# Antenna_Network.net
KiCad netlist of a schematic drawn in Altium Designer
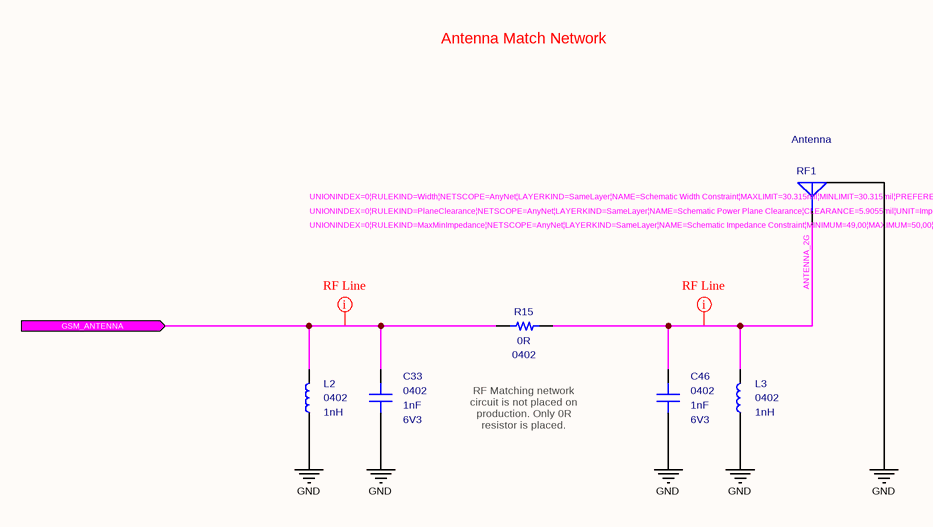
[diagram p0: Antenna Network.SchDoc]

(export (version "E")
  (design (tool "Eeschema 10.0.6"))
  (components
    (comp (ref "C33")
      (value "1nF")
      (footprint "CAPACITOR_0402")
      (description "Capacitor - 1nF [0402] (Ceramic)")
      (fields
        (field (name "MANUFACTURER_PART_NUMBER") "04026C102MAT2A")
        (field (name "MOUSER_PART_NUMBER") "581-04026C102MAT2A")
        (field (name "CASE") "0402")
        (field (name "VOLTAGE") "6V3")
      )
      (libsource (lib "Ovoo_Schematic") (part "Capacitor - 1nF [0402-6V3)"))
    )
    (comp (ref "C46")
      (value "1nF")
      (footprint "CAPACITOR_0402")
      (description "Capacitor - 1nF [0402] (Ceramic)")
      (fields
        (field (name "MANUFACTURER_PART_NUMBER") "04026C102MAT2A")
        (field (name "MOUSER_PART_NUMBER") "581-04026C102MAT2A")
        (field (name "CASE") "0402")
        (field (name "VOLTAGE") "6V3")
      )
      (libsource (lib "Ovoo_Schematic") (part "Capacitor - 1nF [0402-6V3)"))
    )
    (comp (ref "L2")
      (value "1nH")
      (footprint "INDUCTOR_0402")
      (description "Fixed Inductor")
      (fields
        (field (name "MANUFACTURER_PART_NUMBER") "LQG15HN1N0S02D")
        (field (name "MOUSER_PART_NUMBER") "81-LQG15HN1N0S02D")
        (field (name "CASE") "0402")
      )
      (libsource (lib "Ovoo_Schematic") (part "Inductor - 1nH [0402]"))
    )
    (comp (ref "L3")
      (value "1nH")
      (footprint "INDUCTOR_0402")
      (description "Fixed Inductor")
      (fields
        (field (name "MANUFACTURER_PART_NUMBER") "LQG15HN1N0S02D")
        (field (name "MOUSER_PART_NUMBER") "81-LQG15HN1N0S02D")
        (field (name "CASE") "0402")
      )
      (libsource (lib "Ovoo_Schematic") (part "Inductor - 1nH [0402]"))
    )
    (comp (ref "R15")
      (value "0R")
      (footprint "RESISTOR_0402")
      (description "Thick Film Resistors - SMD 1/16 W 0 Ohms")
      (fields
        (field (name "MANUFACTURER_PART_NUMBER") "CRCW04020000Z0ED")
        (field (name "MOUSER_PART_NUMBER") "71-CRCW0402-0-E3")
        (field (name "CASE") "0402")
      )
      (libsource (lib "Ovoo_Schematic") (part "Resistor - 0R"))
    )
    (comp (ref "RF1")
      (value "Antenna")
      (footprint "Connector_IPEX")
      (description "MHF Antenna Socket")
      (libsource (lib "Ovoo_Schematic") (part "Connector - MHF"))
    )
  )
  (nets
    (net (code "1") (name "/ANTENNA_2G") (class "Default")
      (node (ref "C46") (pin "2") (pinfunction "2_2") (pintype "passive"))
      (node (ref "L3") (pin "2") (pinfunction "2_2") (pintype "passive"))
      (node (ref "R15") (pin "1") (pinfunction "1_1") (pintype "passive"))
      (node (ref "RF1") (pin "1") (pinfunction "Signal_1") (pintype "passive"))
    )
    (net (code "2") (name "/GSM_ANTENNA") (class "Default")
      (node (ref "C33") (pin "2") (pinfunction "2_2") (pintype "passive"))
      (node (ref "L2") (pin "2") (pinfunction "2_2") (pintype "passive"))
      (node (ref "R15") (pin "2") (pinfunction "2_2") (pintype "passive"))
    )
    (net (code "3") (name "GND") (class "Default")
      (node (ref "C33") (pin "1") (pinfunction "1_1") (pintype "passive"))
      (node (ref "C46") (pin "1") (pinfunction "1_1") (pintype "passive"))
      (node (ref "L2") (pin "1") (pinfunction "1_1") (pintype "passive"))
      (node (ref "L3") (pin "1") (pinfunction "1_1") (pintype "passive"))
      (node (ref "RF1") (pin "2") (pinfunction "GND_2") (pintype "passive"))
    )
  )
)
